# UD3_1_Supplies.net
KiCad netlist of a schematic drawn in Altium Designer
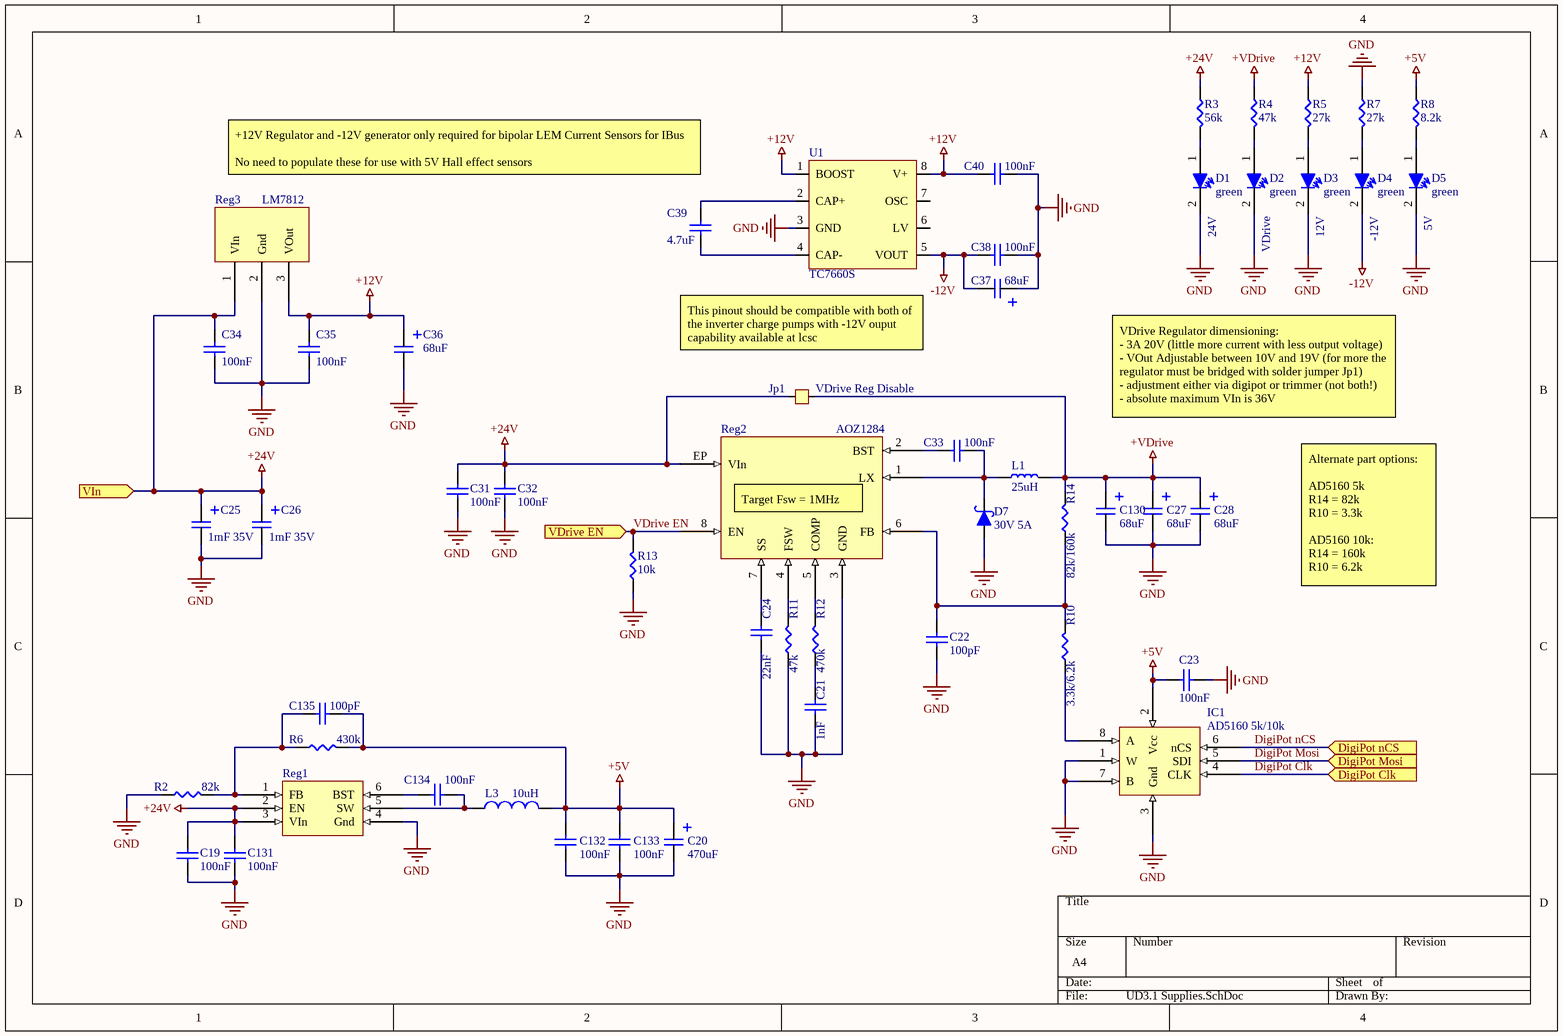
[diagram p0: UD3.1 Supplies.SchDoc]

(export (version "E")
  (design (tool "Eeschema 10.0.6"))
  (components
    (comp (ref "C19") (value "100nF") (footprint "0603") (libsource (lib "stdLib") (part "Cap")))
    (comp (ref "C20")
      (value "470uF")
      (footprint "Elko 6,3 x 11 x 2,5")
      (libsource (lib "stdLib") (part "Cap Polar"))
    )
    (comp (ref "C21") (value "1nF") (footprint "0603") (libsource (lib "stdLib") (part "Cap")))
    (comp (ref "C22") (value "100pF") (footprint "0603") (libsource (lib "stdLib") (part "Cap")))
    (comp (ref "C23") (value "100nF") (footprint "0603") (libsource (lib "stdLib") (part "Cap")))
    (comp (ref "C24") (value "22nF") (footprint "0603") (libsource (lib "stdLib") (part "Cap")))
    (comp (ref "C25")
      (value "1mF 35V")
      (footprint "Elko 13 x 25 x 5")
      (libsource (lib "stdLib") (part "Cap Polar"))
    )
    (comp (ref "C26")
      (value "1mF 35V")
      (footprint "Elko 13 x 25 x 5")
      (libsource (lib "stdLib") (part "Cap Polar"))
    )
    (comp (ref "C27")
      (value "68uF")
      (footprint "Elko 6,3 x 11 x 2,5")
      (libsource (lib "stdLib") (part "Cap Polar"))
    )
    (comp (ref "C28")
      (value "68uF")
      (footprint "Elko 6,3 x 11 x 2,5")
      (libsource (lib "stdLib") (part "Cap Polar"))
    )
    (comp (ref "C31") (value "100nF") (footprint "0603") (libsource (lib "stdLib") (part "Cap")))
    (comp (ref "C32") (value "100nF") (footprint "0603") (libsource (lib "stdLib") (part "Cap")))
    (comp (ref "C33") (value "100nF") (footprint "0603") (libsource (lib "stdLib") (part "Cap")))
    (comp (ref "C34") (value "100nF") (footprint "0603") (libsource (lib "stdLib") (part "Cap")))
    (comp (ref "C35") (value "100nF") (footprint "0603") (libsource (lib "stdLib") (part "Cap")))
    (comp (ref "C36")
      (value "68uF")
      (footprint "Elko 6,3 x 11 x 2,5")
      (libsource (lib "stdLib") (part "Cap Polar"))
    )
    (comp (ref "C37")
      (value "68uF")
      (footprint "Elko 6,3 x 11 x 2,5")
      (libsource (lib "stdLib") (part "Cap Polar"))
    )
    (comp (ref "C38") (value "100nF") (footprint "0603") (libsource (lib "stdLib") (part "Cap")))
    (comp (ref "C39") (value "4.7uF") (footprint "0603") (libsource (lib "stdLib") (part "Cap")))
    (comp (ref "C40") (value "100nF") (footprint "0603") (libsource (lib "stdLib") (part "Cap")))
    (comp (ref "C130")
      (value "68uF")
      (footprint "Elko 6,3 x 11 x 2,5")
      (libsource (lib "stdLib") (part "Cap Polar"))
    )
    (comp (ref "C131") (value "100nF") (footprint "0603") (libsource (lib "stdLib") (part "Cap")))
    (comp (ref "C132") (value "100nF") (footprint "0603") (libsource (lib "stdLib") (part "Cap")))
    (comp (ref "C133") (value "100nF") (footprint "0603") (libsource (lib "stdLib") (part "Cap")))
    (comp (ref "C134") (value "100nF") (footprint "0603") (libsource (lib "stdLib") (part "Cap")))
    (comp (ref "C135") (value "100pF") (footprint "0603") (libsource (lib "stdLib") (part "Cap")))
    (comp (ref "D1")
      (value "green")
      (footprint "1206 Reverse Mount")
      (description "Diode, but it lights up")
      (libsource (lib "stdLib") (part "LED"))
    )
    (comp (ref "D2")
      (value "green")
      (footprint "1206 Reverse Mount")
      (description "Diode, but it lights up")
      (libsource (lib "stdLib") (part "LED"))
    )
    (comp (ref "D3")
      (value "green")
      (footprint "1206 Reverse Mount")
      (description "Diode, but it lights up")
      (libsource (lib "stdLib") (part "LED"))
    )
    (comp (ref "D4")
      (value "green")
      (footprint "1206 Reverse Mount")
      (description "Diode, but it lights up")
      (libsource (lib "stdLib") (part "LED"))
    )
    (comp (ref "D5")
      (value "green")
      (footprint "1206 Reverse Mount")
      (description "Diode, but it lights up")
      (libsource (lib "stdLib") (part "LED"))
    )
    (comp (ref "D7") (value "30V 5A") (footprint "DO-214") (libsource (lib "stdLib") (part "Diode Schottky")))
    (comp (ref "IC1")
      (value "AD5160 5k/10k")
      (footprint "Sot 23-8")
      (description "DigiPot 8bit")
      (libsource (lib "stdLib") (part "AD5160"))
    )
    (comp (ref "Jp1")
      (value "VDrive Reg Disable")
      (footprint "PCB Jumper NO")
      (libsource (lib "stdLib") (part "Jumper"))
    )
    (comp (ref "L1")
      (value "25uH")
      (footprint "Inductor 11x11mm")
      (libsource (lib "stdLib") (part "Inductor High Power"))
    )
    (comp (ref "L3") (value "10uH") (footprint "1008") (libsource (lib "stdLib") (part "Inductor")))
    (comp (ref "R2") (value "82k") (footprint "0603") (libsource (lib "stdLib") (part "Resistor")))
    (comp (ref "R3") (value "56k") (footprint "0603") (libsource (lib "stdLib") (part "Resistor")))
    (comp (ref "R4") (value "47k") (footprint "0603") (libsource (lib "stdLib") (part "Resistor")))
    (comp (ref "R5") (value "27k") (footprint "0603") (libsource (lib "stdLib") (part "Resistor")))
    (comp (ref "R6") (value "430k") (footprint "0603") (libsource (lib "stdLib") (part "Resistor")))
    (comp (ref "R7") (value "27k") (footprint "0603") (libsource (lib "stdLib") (part "Resistor")))
    (comp (ref "R8") (value "8.2k") (footprint "0603") (libsource (lib "stdLib") (part "Resistor")))
    (comp (ref "R10") (value "3.3k/6.2k") (footprint "0603") (libsource (lib "stdLib") (part "Resistor")))
    (comp (ref "R11") (value "47k") (footprint "0603") (libsource (lib "stdLib") (part "Resistor")))
    (comp (ref "R12") (value "470k") (footprint "0603") (libsource (lib "stdLib") (part "Resistor")))
    (comp (ref "R13") (value "10k") (footprint "0603") (libsource (lib "stdLib") (part "Resistor")))
    (comp (ref "R14") (value "82k/160k") (footprint "0603") (libsource (lib "stdLib") (part "Resistor")))
    (comp (ref "Reg1")
      (value "Buck regulator")
      (footprint "TSOT26")
      (libsource (lib "stdLib") (part "AP6320"))
    )
    (comp (ref "Reg2")
      (value "AOZ1284")
      (footprint "SOIC8 EXPOSED")
      (description "Buck Regulator, Internal Switch 4A")
      (libsource (lib "stdLib") (part "AOZ1284"))
    )
    (comp (ref "Reg3")
      (value "LM7812")
      (footprint "TO252 DPAk")
      (description "positive voltage regulator")
      (libsource (lib "stdLib") (part "lm78xx"))
    )
    (comp (ref "U1") (value "TC7660S") (footprint "SOIC8") (libsource (lib "steve lib") (part "TC7660S")))
  )
  (nets
    (net (code "1") (name "+5V") (class "Default")
      (node (ref "C132") (pin "1") (pinfunction "1_1") (pintype "passive"))
      (node (ref "C133") (pin "1") (pinfunction "1_1") (pintype "passive"))
      (node (ref "C135") (pin "1") (pinfunction "1_1") (pintype "passive"))
      (node (ref "C20") (pin "1") (pintype "passive"))
      (node (ref "C23") (pin "2") (pinfunction "2_2") (pintype "passive"))
      (node (ref "IC1") (pin "2") (pinfunction "Vcc_2") (pintype "input"))
      (node (ref "L3") (pin "2") (pinfunction "2_2") (pintype "passive"))
      (node (ref "R6") (pin "2") (pinfunction "2_2") (pintype "passive"))
      (node (ref "R8") (pin "1") (pinfunction "1_1") (pintype "passive"))
    )
    (net (code "2") (name "+12V") (class "Default")
      (node (ref "C35") (pin "2") (pinfunction "2_2") (pintype "passive"))
      (node (ref "C36") (pin "1") (pintype "passive"))
      (node (ref "C40") (pin "2") (pinfunction "2_2") (pintype "passive"))
      (node (ref "R5") (pin "1") (pinfunction "1_1") (pintype "passive"))
      (node (ref "Reg3") (pin "3") (pinfunction "VOut_3") (pintype "passive"))
      (node (ref "U1") (pin "1") (pinfunction "BOOST_1") (pintype "passive"))
      (node (ref "U1") (pin "8") (pinfunction "V+_8") (pintype "passive"))
    )
    (net (code "3") (name "+24V") (class "Default")
      (node (ref "C131") (pin "1") (pinfunction "1_1") (pintype "passive"))
      (node (ref "C19") (pin "2") (pinfunction "2_2") (pintype "passive"))
      (node (ref "C25") (pin "1") (pintype "passive"))
      (node (ref "C26") (pin "1") (pintype "passive"))
      (node (ref "C31") (pin "2") (pinfunction "2_2") (pintype "passive"))
      (node (ref "C32") (pin "2") (pinfunction "2_2") (pintype "passive"))
      (node (ref "C34") (pin "2") (pinfunction "2_2") (pintype "passive"))
      (node (ref "Jp1") (pin "1") (pinfunction "1_1") (pintype "passive"))
      (node (ref "R3") (pin "1") (pinfunction "1_1") (pintype "passive"))
      (node (ref "Reg1") (pin "2") (pinfunction "EN_2") (pintype "input"))
      (node (ref "Reg1") (pin "3") (pinfunction "VIn_3") (pintype "input"))
      (node (ref "Reg2") (pin "EP") (pinfunction "VIn_EP") (pintype "input"))
      (node (ref "Reg3") (pin "1") (pinfunction "VIn_1") (pintype "passive"))
    )
    (net (code "4") (name "+VDrive") (class "Default")
      (node (ref "C130") (pin "1") (pintype "passive"))
      (node (ref "C27") (pin "1") (pintype "passive"))
      (node (ref "C28") (pin "1") (pintype "passive"))
      (node (ref "Jp1") (pin "2") (pinfunction "2_2") (pintype "passive"))
      (node (ref "L1") (pin "2") (pinfunction "2_2") (pintype "passive"))
      (node (ref "R14") (pin "2") (pinfunction "2_2") (pintype "passive"))
      (node (ref "R4") (pin "1") (pinfunction "1_1") (pintype "passive"))
    )
    (net (code "5") (name "-12V") (class "Default")
      (node (ref "C37") (pin "2") (pintype "passive"))
      (node (ref "C38") (pin "2") (pinfunction "2_2") (pintype "passive"))
      (node (ref "D4") (pin "2") (pintype "passive"))
      (node (ref "U1") (pin "5") (pinfunction "VOUT_5") (pintype "passive"))
    )
    (net (code "6") (name "/DigiPot Clk") (class "Default")
      (node (ref "IC1") (pin "4") (pinfunction "CLK_4") (pintype "input"))
    )
    (net (code "7") (name "/DigiPot Mosi") (class "Default")
      (node (ref "IC1") (pin "5") (pinfunction "SDI_5") (pintype "input"))
    )
    (net (code "8") (name "/DigiPot nCS") (class "Default")
      (node (ref "IC1") (pin "6") (pinfunction "nCS_6") (pintype "input"))
    )
    (net (code "9") (name "/VDrive EN") (class "Default")
      (node (ref "R13") (pin "2") (pinfunction "2_2") (pintype "passive"))
      (node (ref "Reg2") (pin "8") (pinfunction "EN_8") (pintype "input"))
    )
    (net (code "10") (name "GND") (class "Default")
      (node (ref "C130") (pin "2") (pintype "passive"))
      (node (ref "C131") (pin "2") (pinfunction "2_2") (pintype "passive"))
      (node (ref "C132") (pin "2") (pinfunction "2_2") (pintype "passive"))
      (node (ref "C133") (pin "2") (pinfunction "2_2") (pintype "passive"))
      (node (ref "C19") (pin "1") (pinfunction "1_1") (pintype "passive"))
      (node (ref "C20") (pin "2") (pintype "passive"))
      (node (ref "C21") (pin "1") (pinfunction "1_1") (pintype "passive"))
      (node (ref "C22") (pin "2") (pinfunction "2_2") (pintype "passive"))
      (node (ref "C23") (pin "1") (pinfunction "1_1") (pintype "passive"))
      (node (ref "C24") (pin "1") (pinfunction "1_1") (pintype "passive"))
      (node (ref "C25") (pin "2") (pintype "passive"))
      (node (ref "C26") (pin "2") (pintype "passive"))
      (node (ref "C27") (pin "2") (pintype "passive"))
      (node (ref "C28") (pin "2") (pintype "passive"))
      (node (ref "C31") (pin "1") (pinfunction "1_1") (pintype "passive"))
      (node (ref "C32") (pin "1") (pinfunction "1_1") (pintype "passive"))
      (node (ref "C34") (pin "1") (pinfunction "1_1") (pintype "passive"))
      (node (ref "C35") (pin "1") (pinfunction "1_1") (pintype "passive"))
      (node (ref "C36") (pin "2") (pintype "passive"))
      (node (ref "C37") (pin "1") (pintype "passive"))
      (node (ref "C38") (pin "1") (pinfunction "1_1") (pintype "passive"))
      (node (ref "C40") (pin "1") (pinfunction "1_1") (pintype "passive"))
      (node (ref "D1") (pin "2") (pintype "passive"))
      (node (ref "D2") (pin "2") (pintype "passive"))
      (node (ref "D3") (pin "2") (pintype "passive"))
      (node (ref "D5") (pin "2") (pintype "passive"))
      (node (ref "D7") (pin "1") (pintype "passive"))
      (node (ref "IC1") (pin "1") (pinfunction "W_1") (pintype "input"))
      (node (ref "IC1") (pin "3") (pinfunction "Gnd_3") (pintype "input"))
      (node (ref "IC1") (pin "7") (pinfunction "B_7") (pintype "input"))
      (node (ref "R11") (pin "1") (pinfunction "1_1") (pintype "passive"))
      (node (ref "R13") (pin "1") (pinfunction "1_1") (pintype "passive"))
      (node (ref "R2") (pin "1") (pinfunction "1_1") (pintype "passive"))
      (node (ref "R7") (pin "1") (pinfunction "1_1") (pintype "passive"))
      (node (ref "Reg1") (pin "4") (pinfunction "Gnd_4") (pintype "input"))
      (node (ref "Reg2") (pin "3") (pinfunction "GND_3") (pintype "input"))
      (node (ref "Reg3") (pin "2") (pinfunction "Gnd_2") (pintype "passive"))
      (node (ref "U1") (pin "3") (pinfunction "GND_3") (pintype "passive"))
    )
    (net (code "11") (name "Net-(C21-Pad2)") (class "Default")
      (node (ref "C21") (pin "2") (pinfunction "2_2") (pintype "passive"))
      (node (ref "R12") (pin "1") (pinfunction "1_1") (pintype "passive"))
    )
    (net (code "12") (name "Net-(D1-Pad1)") (class "Default")
      (node (ref "D1") (pin "1") (pintype "passive"))
      (node (ref "R3") (pin "2") (pinfunction "2_2") (pintype "passive"))
    )
    (net (code "13") (name "Net-(D2-Pad1)") (class "Default")
      (node (ref "D2") (pin "1") (pintype "passive"))
      (node (ref "R4") (pin "2") (pinfunction "2_2") (pintype "passive"))
    )
    (net (code "14") (name "Net-(D3-Pad1)") (class "Default")
      (node (ref "D3") (pin "1") (pintype "passive"))
      (node (ref "R5") (pin "2") (pinfunction "2_2") (pintype "passive"))
    )
    (net (code "15") (name "Net-(D4-Pad1)") (class "Default")
      (node (ref "D4") (pin "1") (pintype "passive"))
      (node (ref "R7") (pin "2") (pinfunction "2_2") (pintype "passive"))
    )
    (net (code "16") (name "Net-(D5-Pad1)") (class "Default")
      (node (ref "D5") (pin "1") (pintype "passive"))
      (node (ref "R8") (pin "2") (pinfunction "2_2") (pintype "passive"))
    )
    (net (code "17") (name "Net-(IC1-A)") (class "Default")
      (node (ref "IC1") (pin "8") (pinfunction "A_8") (pintype "input"))
      (node (ref "R10") (pin "1") (pinfunction "1_1") (pintype "passive"))
    )
    (net (code "18") (name "Net-(Reg1-BST)") (class "Default")
      (node (ref "C134") (pin "1") (pinfunction "1_1") (pintype "passive"))
      (node (ref "Reg1") (pin "6") (pinfunction "BST_6") (pintype "input"))
    )
    (net (code "19") (name "Net-(Reg1-FB)") (class "Default")
      (node (ref "C135") (pin "2") (pinfunction "2_2") (pintype "passive"))
      (node (ref "R2") (pin "2") (pinfunction "2_2") (pintype "passive"))
      (node (ref "R6") (pin "1") (pinfunction "1_1") (pintype "passive"))
      (node (ref "Reg1") (pin "1") (pinfunction "FB_1") (pintype "input"))
    )
    (net (code "20") (name "Net-(Reg1-SW)") (class "Default")
      (node (ref "C134") (pin "2") (pinfunction "2_2") (pintype "passive"))
      (node (ref "L3") (pin "1") (pinfunction "1_1") (pintype "passive"))
      (node (ref "Reg1") (pin "5") (pinfunction "SW_5") (pintype "input"))
    )
    (net (code "21") (name "Net-(Reg2-BST)") (class "Default")
      (node (ref "C33") (pin "2") (pinfunction "2_2") (pintype "passive"))
      (node (ref "Reg2") (pin "2") (pinfunction "BST_2") (pintype "input"))
    )
    (net (code "22") (name "Net-(Reg2-COMP)") (class "Default")
      (node (ref "R12") (pin "2") (pinfunction "2_2") (pintype "passive"))
      (node (ref "Reg2") (pin "5") (pinfunction "COMP_5") (pintype "input"))
    )
    (net (code "23") (name "Net-(Reg2-FB)") (class "Default")
      (node (ref "C22") (pin "1") (pinfunction "1_1") (pintype "passive"))
      (node (ref "R10") (pin "2") (pinfunction "2_2") (pintype "passive"))
      (node (ref "R14") (pin "1") (pinfunction "1_1") (pintype "passive"))
      (node (ref "Reg2") (pin "6") (pinfunction "FB_6") (pintype "input"))
    )
    (net (code "24") (name "Net-(Reg2-FSW)") (class "Default")
      (node (ref "R11") (pin "2") (pinfunction "2_2") (pintype "passive"))
      (node (ref "Reg2") (pin "4") (pinfunction "FSW_4") (pintype "input"))
    )
    (net (code "25") (name "Net-(Reg2-LX)") (class "Default")
      (node (ref "C33") (pin "1") (pinfunction "1_1") (pintype "passive"))
      (node (ref "D7") (pin "2") (pintype "passive"))
      (node (ref "L1") (pin "1") (pinfunction "1_1") (pintype "passive"))
      (node (ref "Reg2") (pin "1") (pinfunction "LX_1") (pintype "input"))
    )
    (net (code "26") (name "Net-(Reg2-SS)") (class "Default")
      (node (ref "C24") (pin "2") (pinfunction "2_2") (pintype "passive"))
      (node (ref "Reg2") (pin "7") (pinfunction "SS_7") (pintype "input"))
    )
    (net (code "27") (name "Net-(U1-CAP+)") (class "Default")
      (node (ref "C39") (pin "1") (pinfunction "1_1") (pintype "passive"))
      (node (ref "U1") (pin "2") (pinfunction "CAP+_2") (pintype "passive"))
    )
    (net (code "28") (name "Net-(U1-CAP-)") (class "Default")
      (node (ref "C39") (pin "2") (pinfunction "2_2") (pintype "passive"))
      (node (ref "U1") (pin "4") (pinfunction "CAP-_4") (pintype "passive"))
    )
    (net (code "29") (name "unconnected-(U1-LV-Pad6)") (class "Default")
      (node (ref "U1") (pin "6") (pinfunction "LV_6") (pintype "passive"))
    )
    (net (code "30") (name "unconnected-(U1-OSC-Pad7)") (class "Default")
      (node (ref "U1") (pin "7") (pinfunction "OSC_7") (pintype "passive"))
    )
  )
)
